# POWER_SUPPLY.net
KiCad netlist of a schematic drawn in Altium Designer
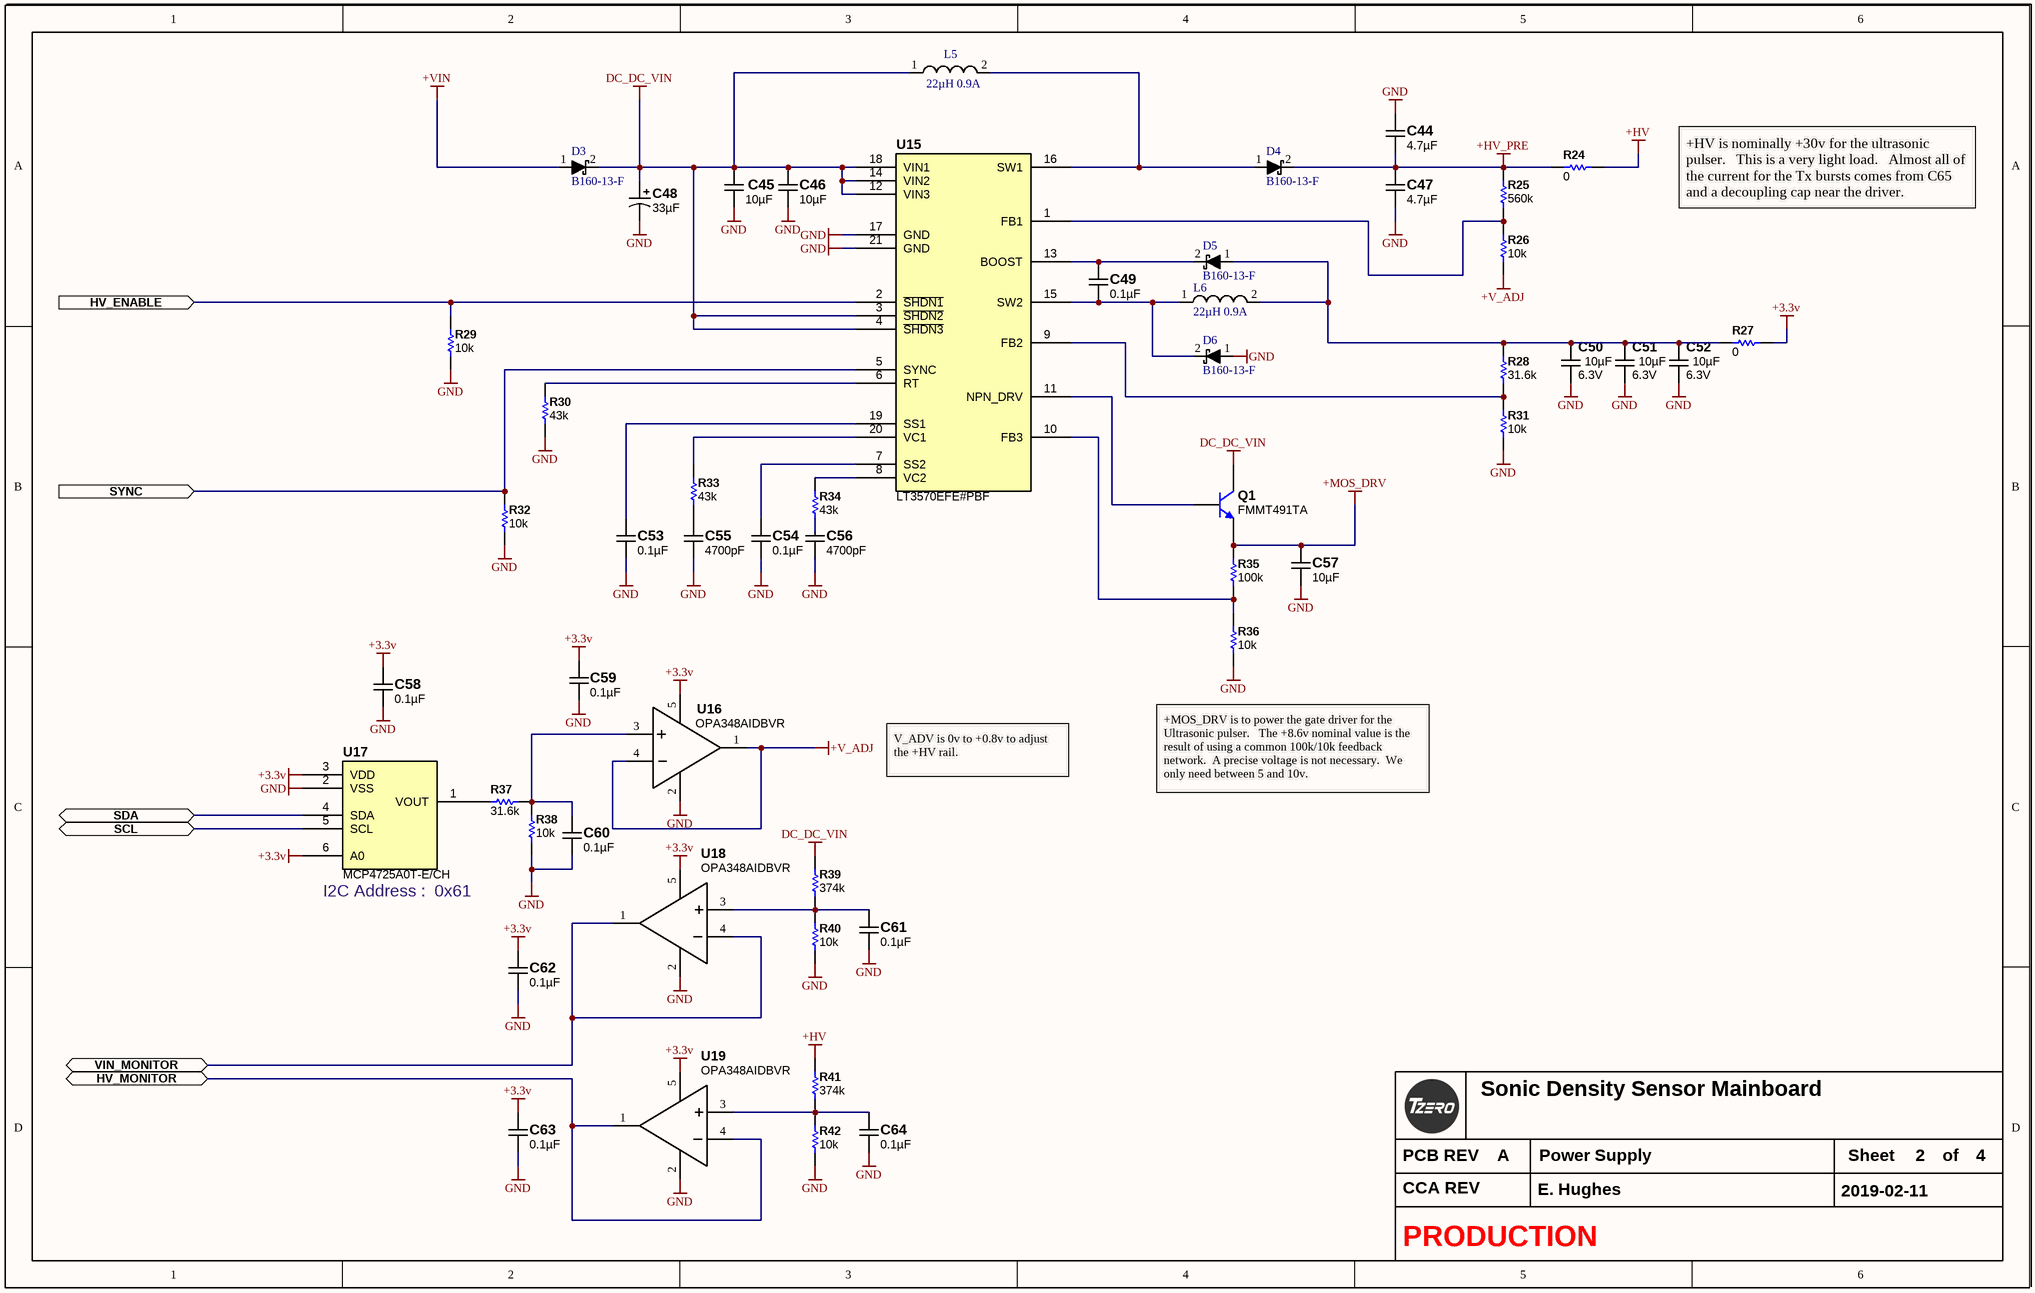
[diagram p0: POWER_SUPPLY.SchDoc]

(export (version "E")
  (design (tool "Eeschema 10.0.6"))
  (components
    (comp (ref "C44")
      (value "4.7µF")
      (footprint "C1210_2.80MM_HD")
      (description "CAP CER 4.7UF 50V X7R 1210")
      (fields
        (field (name "MANUFACTURER PART NUMBER") "CGA6P3X7R1H475M250AB")
        (field (name "MANUFACTURER") "TDK Corporation")
      )
      (libsource (lib "Capacitors - TDK- AEC-Q200") (part "C_2P_NP"))
    )
    (comp (ref "C45")
      (value "10µF")
      (footprint "C1206_1.90MM_HD")
      (description "CAP CER 10UF 35V X7R 1206")
      (fields
        (field (name "MANUFACTURER PART NUMBER") "CGA5L1X7R1V106K160AE")
        (field (name "MANUFACTURER") "TDK Corporation")
      )
      (libsource (lib "Capacitors - TDK- AEC-Q200") (part "C_2P_NP"))
    )
    (comp (ref "C46")
      (value "10µF")
      (footprint "C1206_1.90MM_HD")
      (description "CAP CER 10UF 35V X7R 1206")
      (fields
        (field (name "MANUFACTURER PART NUMBER") "CGA5L1X7R1V106K160AE")
        (field (name "MANUFACTURER") "TDK Corporation")
      )
      (libsource (lib "Capacitors - TDK- AEC-Q200") (part "C_2P_NP"))
    )
    (comp (ref "C47")
      (value "4.7µF")
      (footprint "C1210_2.80MM_HD")
      (description "CAP CER 4.7UF 50V X7R 1210")
      (fields
        (field (name "MANUFACTURER PART NUMBER") "CGA6P3X7R1H475M250AB")
        (field (name "MANUFACTURER") "TDK Corporation")
      )
      (libsource (lib "Capacitors - TDK- AEC-Q200") (part "C_2P_NP"))
    )
    (comp (ref "C48")
      (value "33µF")
      (footprint "C_ALU_C")
      (description "CAP ALUM 33UF 25V 20% SMD")
      (fields
        (field (name "MANUFACTURER PART NUMBER") "EEE-FK1E330UR")
        (field (name "MANUFACTURER") "Panasonic Electronic Components")
      )
      (libsource (lib "Capacitors") (part "C_2P_P"))
    )
    (comp (ref "C49")
      (value "0.1µF")
      (footprint "C0603_0.90MM_HD")
      (description "CAP CER 0.1UF 50V X7R 0603")
      (fields
        (field (name "MANUFACTURER PART NUMBER") "CGA3E2X7R1H104K080AE")
        (field (name "MANUFACTURER") "TDK Corporation")
      )
      (libsource (lib "Capacitors - TDK- AEC-Q200") (part "C_2P_NP"))
    )
    (comp (ref "C50")
      (value "10µF")
      (footprint "C0805_1.45MM_MD")
      (description "CAP CER 10UF 6.3V X7R 0805")
      (fields
        (field (name "MANUFACTURER PART NUMBER") "CGA4J1X7R0J106K125AC")
        (field (name "MANUFACTURER") "TDK Corporation")
        (field (name "VOLTAGE - RATED") "6.3V")
      )
      (libsource (lib "Capacitors - TDK- AEC-Q200") (part "C_2P_NP"))
    )
    (comp (ref "C51")
      (value "10µF")
      (footprint "C0805_1.45MM_MD")
      (description "CAP CER 10UF 6.3V X7R 0805")
      (fields
        (field (name "MANUFACTURER PART NUMBER") "CGA4J1X7R0J106K125AC")
        (field (name "MANUFACTURER") "TDK Corporation")
        (field (name "VOLTAGE - RATED") "6.3V")
      )
      (libsource (lib "Capacitors - TDK- AEC-Q200") (part "C_2P_NP"))
    )
    (comp (ref "C52")
      (value "10µF")
      (footprint "C0805_1.45MM_MD")
      (description "CAP CER 10UF 6.3V X7R 0805")
      (fields
        (field (name "MANUFACTURER PART NUMBER") "CGA4J1X7R0J106K125AC")
        (field (name "MANUFACTURER") "TDK Corporation")
        (field (name "VOLTAGE - RATED") "6.3V")
      )
      (libsource (lib "Capacitors - TDK- AEC-Q200") (part "C_2P_NP"))
    )
    (comp (ref "C53")
      (value "0.1µF")
      (footprint "C0603_0.90MM_HD")
      (description "CAP CER 0.1UF 50V X7R 0603")
      (fields
        (field (name "MANUFACTURER PART NUMBER") "CGA3E2X7R1H104K080AE")
        (field (name "MANUFACTURER") "TDK Corporation")
      )
      (libsource (lib "Capacitors - TDK- AEC-Q200") (part "C_2P_NP"))
    )
    (comp (ref "C54")
      (value "0.1µF")
      (footprint "C0603_0.90MM_HD")
      (description "CAP CER 0.1UF 50V X7R 0603")
      (fields
        (field (name "MANUFACTURER PART NUMBER") "CGA3E2X7R1H104K080AE")
        (field (name "MANUFACTURER") "TDK Corporation")
      )
      (libsource (lib "Capacitors - TDK- AEC-Q200") (part "C_2P_NP"))
    )
    (comp (ref "C55")
      (value "4700pF")
      (footprint "C0603_0.95MM_HD")
      (description "CAP CER 4700PF 50V X7R 0603")
      (fields
        (field (name "MANUFACTURER PART NUMBER") "CGA3E2X7R1H472K080AE")
        (field (name "MANUFACTURER") "TDK Corporation")
      )
      (libsource (lib "Capacitors - TDK- AEC-Q200") (part "C_2P_NP"))
    )
    (comp (ref "C56")
      (value "4700pF")
      (footprint "C0603_0.95MM_HD")
      (description "CAP CER 4700PF 50V X7R 0603")
      (fields
        (field (name "MANUFACTURER PART NUMBER") "CGA3E2X7R1H472K080AE")
        (field (name "MANUFACTURER") "TDK Corporation")
      )
      (libsource (lib "Capacitors - TDK- AEC-Q200") (part "C_2P_NP"))
    )
    (comp (ref "C57")
      (value "10µF")
      (footprint "C1206_1.90MM_HD")
      (description "CAP CER 10UF 35V X7R 1206")
      (fields
        (field (name "MANUFACTURER PART NUMBER") "CGA5L1X7R1V106K160AE")
        (field (name "MANUFACTURER") "TDK Corporation")
      )
      (libsource (lib "Capacitors - TDK- AEC-Q200") (part "C_2P_NP"))
    )
    (comp (ref "C58")
      (value "0.1µF")
      (footprint "C0603_0.90MM_HD")
      (description "CAP CER 0.1UF 50V X7R 0603")
      (fields
        (field (name "MANUFACTURER PART NUMBER") "CGA3E2X7R1H104K080AE")
        (field (name "MANUFACTURER") "TDK Corporation")
      )
      (libsource (lib "Capacitors - TDK- AEC-Q200") (part "C_2P_NP"))
    )
    (comp (ref "C59")
      (value "0.1µF")
      (footprint "C0603_0.90MM_HD")
      (description "CAP CER 0.1UF 50V X7R 0603")
      (fields
        (field (name "MANUFACTURER PART NUMBER") "CGA3E2X7R1H104K080AE")
        (field (name "MANUFACTURER") "TDK Corporation")
      )
      (libsource (lib "Capacitors - TDK- AEC-Q200") (part "C_2P_NP"))
    )
    (comp (ref "C60")
      (value "0.1µF")
      (footprint "C0603_0.90MM_HD")
      (description "CAP CER 0.1UF 50V X7R 0603")
      (fields
        (field (name "MANUFACTURER PART NUMBER") "CGA3E2X7R1H104K080AE")
        (field (name "MANUFACTURER") "TDK Corporation")
      )
      (libsource (lib "Capacitors - TDK- AEC-Q200") (part "C_2P_NP"))
    )
    (comp (ref "C61")
      (value "0.1µF")
      (footprint "C0603_0.90MM_HD")
      (description "CAP CER 0.1UF 50V X7R 0603")
      (fields
        (field (name "MANUFACTURER PART NUMBER") "CGA3E2X7R1H104K080AE")
        (field (name "MANUFACTURER") "TDK Corporation")
      )
      (libsource (lib "Capacitors - TDK- AEC-Q200") (part "C_2P_NP"))
    )
    (comp (ref "C62")
      (value "0.1µF")
      (footprint "C0603_0.90MM_HD")
      (description "CAP CER 0.1UF 50V X7R 0603")
      (fields
        (field (name "MANUFACTURER PART NUMBER") "CGA3E2X7R1H104K080AE")
        (field (name "MANUFACTURER") "TDK Corporation")
      )
      (libsource (lib "Capacitors - TDK- AEC-Q200") (part "C_2P_NP"))
    )
    (comp (ref "C63")
      (value "0.1µF")
      (footprint "C0603_0.90MM_HD")
      (description "CAP CER 0.1UF 50V X7R 0603")
      (fields
        (field (name "MANUFACTURER PART NUMBER") "CGA3E2X7R1H104K080AE")
        (field (name "MANUFACTURER") "TDK Corporation")
      )
      (libsource (lib "Capacitors - TDK- AEC-Q200") (part "C_2P_NP"))
    )
    (comp (ref "C64")
      (value "0.1µF")
      (footprint "C0603_0.90MM_HD")
      (description "CAP CER 0.1UF 50V X7R 0603")
      (fields
        (field (name "MANUFACTURER PART NUMBER") "CGA3E2X7R1H104K080AE")
        (field (name "MANUFACTURER") "TDK Corporation")
      )
      (libsource (lib "Capacitors - TDK- AEC-Q200") (part "C_2P_NP"))
    )
    (comp (ref "D3")
      (value "B160-13-F")
      (footprint "D_SMA_P")
      (description "DIODE SCHOTTKY 60V 1A SMA")
      (fields (field (name "MANUFACTURER") "Diodes Inc"))
      (libsource (lib "Diodes") (part "DS_1A_2C"))
    )
    (comp (ref "D4")
      (value "B160-13-F")
      (footprint "D_SMA_P")
      (description "DIODE SCHOTTKY 60V 1A SMA")
      (fields (field (name "MANUFACTURER") "Diodes Inc"))
      (libsource (lib "Diodes") (part "DS_1A_2C"))
    )
    (comp (ref "D5")
      (value "B160-13-F")
      (footprint "D_SMA_P")
      (description "DIODE SCHOTTKY 60V 1A SMA")
      (fields (field (name "MANUFACTURER") "Diodes Inc"))
      (libsource (lib "Diodes") (part "DS_1A_2C"))
    )
    (comp (ref "D6")
      (value "B160-13-F")
      (footprint "D_SMA_P")
      (description "DIODE SCHOTTKY 60V 1A SMA")
      (fields (field (name "MANUFACTURER") "Diodes Inc"))
      (libsource (lib "Diodes") (part "DS_1A_2C"))
    )
    (comp (ref "L5")
      (value "22µH 0.9A")
      (footprint "L_NRS5020")
      (description "Inductor 22µH 0.9A")
      (fields (field (name "PART NUMBER") "NRS5020T220MMGJ") (field (name "MANUFACTURER") "Taiyo Yuden"))
      (libsource (lib "Inductors") (part "L_2P"))
    )
    (comp (ref "L6")
      (value "22µH 0.9A")
      (footprint "L_NRS5020")
      (description "Inductor 22µH 0.9A")
      (fields (field (name "PART NUMBER") "NRS5020T220MMGJ") (field (name "MANUFACTURER") "Taiyo Yuden"))
      (libsource (lib "Inductors") (part "L_2P"))
    )
    (comp (ref "Q1")
      (value "FMMT491TA")
      (footprint "SOT-23")
      (description "TRANS NPN 60V 1A SOT23-3")
      (fields (field (name "MANUFACTURER") "Diodes Zetex"))
      (libsource (lib "eTransistor") (part "FMMT491TA"))
    )
    (comp (ref "R24")
      (value "0")
      (footprint "R0603_0.55MM_HD")
      (description "RES 0.0 OHM 1/10W JUMP 0603 SMD")
      (fields
        (field (name "MANUFACTURER PART NUMBER") "ERJ-3GEY0R00V")
        (field (name "MANUFACTURER") "Panasonic Electronic Components")
      )
      (libsource (lib "Resistors - Panasonic - AEC-Q200") (part "R_2P"))
    )
    (comp (ref "R25")
      (value "560k")
      (footprint "R0603_0.55MM_HD")
      (description "RES 560K OHM 1/10W 1% 0603 SMD")
      (fields
        (field (name "MANUFACTURER PART NUMBER") "ERJ-3EKF5603V")
        (field (name "MANUFACTURER") "Panasonic Electronic Components")
      )
      (libsource (lib "Resistors - Panasonic - AEC-Q200") (part "R_2P"))
    )
    (comp (ref "R26")
      (value "10k")
      (footprint "R0603_0.55MM_HD")
      (description "RES 10K OHM 1/10W 1% 0603 SMD")
      (fields
        (field (name "MANUFACTURER PART NUMBER") "ERJ-3EKF1002V")
        (field (name "MANUFACTURER") "Panasonic Electronic Components")
      )
      (libsource (lib "Resistors - Panasonic - AEC-Q200") (part "R_2P"))
    )
    (comp (ref "R27")
      (value "0")
      (footprint "R0603_0.55MM_HD")
      (description "RES 0.0 OHM 1/10W JUMP 0603 SMD")
      (fields
        (field (name "MANUFACTURER PART NUMBER") "ERJ-3GEY0R00V")
        (field (name "MANUFACTURER") "Panasonic Electronic Components")
      )
      (libsource (lib "Resistors - Panasonic - AEC-Q200") (part "R_2P"))
    )
    (comp (ref "R28")
      (value "31.6k")
      (footprint "R0603_0.55MM_HD")
      (description "RES 31.6K OHM 1/10W 1% 0603 SMD")
      (fields
        (field (name "MANUFACTURER PART NUMBER") "ERJ-3EKF3162V")
        (field (name "MANUFACTURER") "Panasonic Electronic Components")
      )
      (libsource (lib "Resistors - Panasonic - AEC-Q200") (part "R_2P"))
    )
    (comp (ref "R29")
      (value "10k")
      (footprint "R0603_0.55MM_HD")
      (description "RES 10K OHM 1/10W 1% 0603 SMD")
      (fields
        (field (name "MANUFACTURER PART NUMBER") "ERJ-3EKF1002V")
        (field (name "MANUFACTURER") "Panasonic Electronic Components")
      )
      (libsource (lib "Resistors - Panasonic - AEC-Q200") (part "R_2P"))
    )
    (comp (ref "R30")
      (value "43k")
      (footprint "R0603_0.55MM_HD")
      (description "RES 43K OHM 1/10W 1% 0603 SMD")
      (fields
        (field (name "MANUFACTURER PART NUMBER") "ERJ-3EKF4302V")
        (field (name "MANUFACTURER") "Panasonic Electronic Components")
      )
      (libsource (lib "Resistors - Panasonic - AEC-Q200") (part "R_2P"))
    )
    (comp (ref "R31")
      (value "10k")
      (footprint "R0603_0.55MM_HD")
      (description "RES 10K OHM 1/10W 1% 0603 SMD")
      (fields
        (field (name "MANUFACTURER PART NUMBER") "ERJ-3EKF1002V")
        (field (name "MANUFACTURER") "Panasonic Electronic Components")
      )
      (libsource (lib "Resistors - Panasonic - AEC-Q200") (part "R_2P"))
    )
    (comp (ref "R32")
      (value "10k")
      (footprint "R0603_0.55MM_HD")
      (description "RES 10K OHM 1/10W 1% 0603 SMD")
      (fields
        (field (name "MANUFACTURER PART NUMBER") "ERJ-3EKF1002V")
        (field (name "MANUFACTURER") "Panasonic Electronic Components")
      )
      (libsource (lib "Resistors - Panasonic - AEC-Q200") (part "R_2P"))
    )
    (comp (ref "R33")
      (value "43k")
      (footprint "R0603_0.55MM_HD")
      (description "RES 43K OHM 1/10W 1% 0603 SMD")
      (fields
        (field (name "MANUFACTURER PART NUMBER") "ERJ-3EKF4302V")
        (field (name "MANUFACTURER") "Panasonic Electronic Components")
      )
      (libsource (lib "Resistors - Panasonic - AEC-Q200") (part "R_2P"))
    )
    (comp (ref "R34")
      (value "43k")
      (footprint "R0603_0.55MM_HD")
      (description "RES 43K OHM 1/10W 1% 0603 SMD")
      (fields
        (field (name "MANUFACTURER PART NUMBER") "ERJ-3EKF4302V")
        (field (name "MANUFACTURER") "Panasonic Electronic Components")
      )
      (libsource (lib "Resistors - Panasonic - AEC-Q200") (part "R_2P"))
    )
    (comp (ref "R35")
      (value "100k")
      (footprint "R0603_0.55MM_HD")
      (description "RES 100K OHM 1/10W 1% 0603 SMD")
      (fields
        (field (name "MANUFACTURER PART NUMBER") "ERJ-3EKF1003V")
        (field (name "MANUFACTURER") "Panasonic Electronic Components")
      )
      (libsource (lib "Resistors - Panasonic - AEC-Q200") (part "R_2P"))
    )
    (comp (ref "R36")
      (value "10k")
      (footprint "R0603_0.55MM_HD")
      (description "RES 10K OHM 1/10W 1% 0603 SMD")
      (fields
        (field (name "MANUFACTURER PART NUMBER") "ERJ-3EKF1002V")
        (field (name "MANUFACTURER") "Panasonic Electronic Components")
      )
      (libsource (lib "Resistors - Panasonic - AEC-Q200") (part "R_2P"))
    )
    (comp (ref "R37")
      (value "31.6k")
      (footprint "R0603_0.55MM_HD")
      (description "RES 31.6K OHM 1/10W 1% 0603 SMD")
      (fields
        (field (name "MANUFACTURER PART NUMBER") "ERJ-3EKF3162V")
        (field (name "MANUFACTURER") "Panasonic Electronic Components")
      )
      (libsource (lib "Resistors - Panasonic - AEC-Q200") (part "R_2P"))
    )
    (comp (ref "R38")
      (value "10k")
      (footprint "R0603_0.55MM_HD")
      (description "RES 10K OHM 1/10W 1% 0603 SMD")
      (fields
        (field (name "MANUFACTURER PART NUMBER") "ERJ-3EKF1002V")
        (field (name "MANUFACTURER") "Panasonic Electronic Components")
      )
      (libsource (lib "Resistors - Panasonic - AEC-Q200") (part "R_2P"))
    )
    (comp (ref "R39")
      (value "374k")
      (footprint "R0603_0.55MM_HD")
      (description "RES 374K OHM 1/10W 1% 0603 SMD")
      (fields
        (field (name "MANUFACTURER PART NUMBER") "ERJ-3EKF3743V")
        (field (name "MANUFACTURER") "Panasonic Electronic Components")
      )
      (libsource (lib "Resistors - Panasonic - AEC-Q200") (part "R_2P"))
    )
    (comp (ref "R40")
      (value "10k")
      (footprint "R0603_0.55MM_HD")
      (description "RES 10K OHM 1/10W 1% 0603 SMD")
      (fields
        (field (name "MANUFACTURER PART NUMBER") "ERJ-3EKF1002V")
        (field (name "MANUFACTURER") "Panasonic Electronic Components")
      )
      (libsource (lib "Resistors - Panasonic - AEC-Q200") (part "R_2P"))
    )
    (comp (ref "R41")
      (value "374k")
      (footprint "R0603_0.55MM_HD")
      (description "RES 374K OHM 1/10W 1% 0603 SMD")
      (fields
        (field (name "MANUFACTURER PART NUMBER") "ERJ-3EKF3743V")
        (field (name "MANUFACTURER") "Panasonic Electronic Components")
      )
      (libsource (lib "Resistors - Panasonic - AEC-Q200") (part "R_2P"))
    )
    (comp (ref "R42")
      (value "10k")
      (footprint "R0603_0.55MM_HD")
      (description "RES 10K OHM 1/10W 1% 0603 SMD")
      (fields
        (field (name "MANUFACTURER PART NUMBER") "ERJ-3EKF1002V")
        (field (name "MANUFACTURER") "Panasonic Electronic Components")
      )
      (libsource (lib "Resistors - Panasonic - AEC-Q200") (part "R_2P"))
    )
    (comp (ref "U15")
      (value "LT3570EFE#PBF")
      (footprint "TSOP65P640X120_HS-21N")
      (description "IC REG BUCK/BST/LINEAR 20TSSOP")
      (fields (field (name "MANUFACTURER") "Linear Technology"))
      (libsource (lib "eIC") (part "LT3570EFE#PBF"))
    )
    (comp (ref "U16")
      (value "OPA348AIDBVR")
      (footprint "SOT23-5")
      (description "IC OPAMP GP 1MHZ RRO SOT23-5")
      (fields (field (name "MANUFACTURER") "Texas Instruments"))
      (libsource (lib "eOPAMP") (part "OPA348AIDBVR"))
    )
    (comp (ref "U17")
      (value "MCP4725A0T-E/CH")
      (footprint "SOT95P245X145-6L")
      (description "IC DAC 12BIT W/I2C SOT23A-6")
      (fields (field (name "MANUFACTURER") "Microchip"))
      (libsource (lib "eIC") (part "MCP4725A0T-E/CH"))
    )
    (comp (ref "U18")
      (value "OPA348AIDBVR")
      (footprint "SOT23-5")
      (description "IC OPAMP GP 1MHZ RRO SOT23-5")
      (fields (field (name "MANUFACTURER") "Texas Instruments"))
      (libsource (lib "eOPAMP") (part "OPA348AIDBVR"))
    )
    (comp (ref "U19")
      (value "OPA348AIDBVR")
      (footprint "SOT23-5")
      (description "IC OPAMP GP 1MHZ RRO SOT23-5")
      (fields (field (name "MANUFACTURER") "Texas Instruments"))
      (libsource (lib "eOPAMP") (part "OPA348AIDBVR"))
    )
  )
  (nets
    (net (code "1") (name "+3.3v") (class "Default")
      (node (ref "C58") (pin "2") (pinfunction "1_2") (pintype "passive"))
      (node (ref "C59") (pin "2") (pinfunction "1_2") (pintype "passive"))
      (node (ref "C62") (pin "2") (pinfunction "1_2") (pintype "passive"))
      (node (ref "C63") (pin "2") (pinfunction "1_2") (pintype "passive"))
      (node (ref "R27") (pin "1") (pinfunction "1_1") (pintype "passive"))
      (node (ref "U16") (pin "5") (pinfunction "VCC_5") (pintype "passive"))
      (node (ref "U17") (pin "3") (pinfunction "VDD_3") (pintype "passive"))
      (node (ref "U17") (pin "6") (pinfunction "A0_6") (pintype "passive"))
      (node (ref "U18") (pin "5") (pinfunction "VCC_5") (pintype "passive"))
      (node (ref "U19") (pin "5") (pinfunction "VCC_5") (pintype "passive"))
    )
    (net (code "2") (name "+HV") (class "Default")
      (node (ref "R24") (pin "1") (pinfunction "1_1") (pintype "passive"))
      (node (ref "R41") (pin "2") (pinfunction "2_2") (pintype "passive"))
    )
    (net (code "3") (name "+HV_PRE") (class "Default")
      (node (ref "C44") (pin "1") (pinfunction "1_1") (pintype "passive"))
      (node (ref "C47") (pin "2") (pinfunction "1_2") (pintype "passive"))
      (node (ref "D4") (pin "2") (pinfunction "K_2") (pintype "passive"))
      (node (ref "R24") (pin "2") (pinfunction "2_2") (pintype "passive"))
      (node (ref "R25") (pin "2") (pinfunction "2_2") (pintype "passive"))
    )
    (net (code "4") (name "+MOS_DRV") (class "Default")
      (node (ref "C57") (pin "2") (pinfunction "1_2") (pintype "passive"))
      (node (ref "Q1") (pin "2") (pinfunction "E_2") (pintype "passive"))
      (node (ref "R35") (pin "2") (pinfunction "2_2") (pintype "passive"))
    )
    (net (code "5") (name "+VIN") (class "Default")
      (node (ref "D3") (pin "1") (pinfunction "A_1") (pintype "passive"))
    )
    (net (code "6") (name "+V_ADJ") (class "Default")
      (node (ref "R26") (pin "1") (pinfunction "1_1") (pintype "passive"))
      (node (ref "U16") (pin "1") (pinfunction "OUT_1") (pintype "passive"))
      (node (ref "U16") (pin "4") (pinfunction "-_4") (pintype "passive"))
    )
    (net (code "7") (name "/HV_ENABLE") (class "Default")
      (node (ref "R29") (pin "2") (pinfunction "2_2") (pintype "passive"))
      (node (ref "U15") (pin "2") (pinfunction "~{SHDN1}_2") (pintype "passive"))
    )
    (net (code "8") (name "/HV_MONITOR") (class "Default")
      (node (ref "U19") (pin "1") (pinfunction "OUT_1") (pintype "passive"))
      (node (ref "U19") (pin "4") (pinfunction "-_4") (pintype "passive"))
    )
    (net (code "9") (name "/SCL") (class "Default")
      (node (ref "U17") (pin "5") (pinfunction "SCL_5") (pintype "passive"))
    )
    (net (code "10") (name "/SDA") (class "Default")
      (node (ref "U17") (pin "4") (pinfunction "SDA_4") (pintype "passive"))
    )
    (net (code "11") (name "/SYNC") (class "Default")
      (node (ref "R32") (pin "2") (pinfunction "2_2") (pintype "passive"))
      (node (ref "U15") (pin "5") (pinfunction "SYNC_5") (pintype "passive"))
    )
    (net (code "12") (name "/VIN_MONITOR") (class "Default")
      (node (ref "U18") (pin "1") (pinfunction "OUT_1") (pintype "passive"))
      (node (ref "U18") (pin "4") (pinfunction "-_4") (pintype "passive"))
    )
    (net (code "13") (name "DC_DC_VIN") (class "Default")
      (node (ref "C45") (pin "2") (pinfunction "1_2") (pintype "passive"))
      (node (ref "C46") (pin "2") (pinfunction "1_2") (pintype "passive"))
      (node (ref "C48") (pin "1") (pinfunction "1_1") (pintype "passive"))
      (node (ref "D3") (pin "2") (pinfunction "K_2") (pintype "passive"))
      (node (ref "L5") (pin "1") (pinfunction "1_1") (pintype "passive"))
      (node (ref "Q1") (pin "3") (pinfunction "C_3") (pintype "passive"))
      (node (ref "R39") (pin "2") (pinfunction "2_2") (pintype "passive"))
      (node (ref "U15") (pin "12") (pinfunction "VIN3_12") (pintype "passive"))
      (node (ref "U15") (pin "14") (pinfunction "VIN2_14") (pintype "passive"))
      (node (ref "U15") (pin "18") (pinfunction "VIN1_18") (pintype "passive"))
      (node (ref "U15") (pin "3") (pinfunction "~{SHDN2}_3") (pintype "passive"))
      (node (ref "U15") (pin "4") (pinfunction "~{SHDN3}_4") (pintype "passive"))
    )
    (net (code "14") (name "GND") (class "Default")
      (node (ref "C44") (pin "2") (pinfunction "1_2") (pintype "passive"))
      (node (ref "C45") (pin "1") (pinfunction "1_1") (pintype "passive"))
      (node (ref "C46") (pin "1") (pinfunction "1_1") (pintype "passive"))
      (node (ref "C47") (pin "1") (pinfunction "1_1") (pintype "passive"))
      (node (ref "C48") (pin "2") (pinfunction "1_2") (pintype "passive"))
      (node (ref "C50") (pin "1") (pinfunction "1_1") (pintype "passive"))
      (node (ref "C51") (pin "1") (pinfunction "1_1") (pintype "passive"))
      (node (ref "C52") (pin "1") (pinfunction "1_1") (pintype "passive"))
      (node (ref "C53") (pin "1") (pinfunction "1_1") (pintype "passive"))
      (node (ref "C54") (pin "1") (pinfunction "1_1") (pintype "passive"))
      (node (ref "C55") (pin "1") (pinfunction "1_1") (pintype "passive"))
      (node (ref "C56") (pin "1") (pinfunction "1_1") (pintype "passive"))
      (node (ref "C57") (pin "1") (pinfunction "1_1") (pintype "passive"))
      (node (ref "C58") (pin "1") (pinfunction "1_1") (pintype "passive"))
      (node (ref "C59") (pin "1") (pinfunction "1_1") (pintype "passive"))
      (node (ref "C60") (pin "1") (pinfunction "1_1") (pintype "passive"))
      (node (ref "C61") (pin "1") (pinfunction "1_1") (pintype "passive"))
      (node (ref "C62") (pin "1") (pinfunction "1_1") (pintype "passive"))
      (node (ref "C63") (pin "1") (pinfunction "1_1") (pintype "passive"))
      (node (ref "C64") (pin "1") (pinfunction "1_1") (pintype "passive"))
      (node (ref "D6") (pin "1") (pinfunction "A_1") (pintype "passive"))
      (node (ref "R29") (pin "1") (pinfunction "1_1") (pintype "passive"))
      (node (ref "R30") (pin "1") (pinfunction "1_1") (pintype "passive"))
      (node (ref "R31") (pin "1") (pinfunction "1_1") (pintype "passive"))
      (node (ref "R32") (pin "1") (pinfunction "1_1") (pintype "passive"))
      (node (ref "R36") (pin "1") (pinfunction "1_1") (pintype "passive"))
      (node (ref "R38") (pin "1") (pinfunction "1_1") (pintype "passive"))
      (node (ref "R40") (pin "1") (pinfunction "1_1") (pintype "passive"))
      (node (ref "R42") (pin "1") (pinfunction "1_1") (pintype "passive"))
      (node (ref "U15") (pin "17") (pinfunction "GND_17") (pintype "passive"))
      (node (ref "U15") (pin "21") (pinfunction "GND_21") (pintype "passive"))
      (node (ref "U16") (pin "2") (pinfunction "GND_2") (pintype "passive"))
      (node (ref "U17") (pin "2") (pinfunction "VSS_2") (pintype "passive"))
      (node (ref "U18") (pin "2") (pinfunction "GND_2") (pintype "passive"))
      (node (ref "U19") (pin "2") (pinfunction "GND_2") (pintype "passive"))
    )
    (net (code "15") (name "Net-(C55-1-Pad2)") (class "Default")
      (node (ref "C55") (pin "2") (pinfunction "1_2") (pintype "passive"))
      (node (ref "R33") (pin "1") (pinfunction "1_1") (pintype "passive"))
    )
    (net (code "16") (name "Net-(C56-1-Pad2)") (class "Default")
      (node (ref "C56") (pin "2") (pinfunction "1_2") (pintype "passive"))
      (node (ref "R34") (pin "1") (pinfunction "1_1") (pintype "passive"))
    )
    (net (code "17") (name "Net-(D4-A)") (class "Default")
      (node (ref "D4") (pin "1") (pinfunction "A_1") (pintype "passive"))
      (node (ref "L5") (pin "2") (pinfunction "2_2") (pintype "passive"))
      (node (ref "U15") (pin "16") (pinfunction "SW1_16") (pintype "passive"))
    )
    (net (code "18") (name "Net-(D5-A)") (class "Default")
      (node (ref "C50") (pin "2") (pinfunction "1_2") (pintype "passive"))
      (node (ref "C51") (pin "2") (pinfunction "1_2") (pintype "passive"))
      (node (ref "C52") (pin "2") (pinfunction "1_2") (pintype "passive"))
      (node (ref "D5") (pin "1") (pinfunction "A_1") (pintype "passive"))
      (node (ref "L6") (pin "2") (pinfunction "2_2") (pintype "passive"))
      (node (ref "R27") (pin "2") (pinfunction "2_2") (pintype "passive"))
      (node (ref "R28") (pin "2") (pinfunction "2_2") (pintype "passive"))
    )
    (net (code "19") (name "Net-(D5-K)") (class "Default")
      (node (ref "C49") (pin "2") (pinfunction "1_2") (pintype "passive"))
      (node (ref "D5") (pin "2") (pinfunction "K_2") (pintype "passive"))
      (node (ref "U15") (pin "13") (pinfunction "BOOST_13") (pintype "passive"))
    )
    (net (code "20") (name "Net-(D6-K)") (class "Default")
      (node (ref "C49") (pin "1") (pinfunction "1_1") (pintype "passive"))
      (node (ref "D6") (pin "2") (pinfunction "K_2") (pintype "passive"))
      (node (ref "L6") (pin "1") (pinfunction "1_1") (pintype "passive"))
      (node (ref "U15") (pin "15") (pinfunction "SW2_15") (pintype "passive"))
    )
    (net (code "21") (name "Net-(Q1-B)") (class "Default")
      (node (ref "Q1") (pin "1") (pinfunction "B_1") (pintype "passive"))
      (node (ref "U15") (pin "11") (pinfunction "NPN_DRV_11") (pintype "passive"))
    )
    (net (code "22") (name "Net-(U15-FB1)") (class "Default")
      (node (ref "R25") (pin "1") (pinfunction "1_1") (pintype "passive"))
      (node (ref "R26") (pin "2") (pinfunction "2_2") (pintype "passive"))
      (node (ref "U15") (pin "1") (pinfunction "FB1_1") (pintype "passive"))
    )
    (net (code "23") (name "Net-(U15-FB2)") (class "Default")
      (node (ref "R28") (pin "1") (pinfunction "1_1") (pintype "passive"))
      (node (ref "R31") (pin "2") (pinfunction "2_2") (pintype "passive"))
      (node (ref "U15") (pin "9") (pinfunction "FB2_9") (pintype "passive"))
    )
    (net (code "24") (name "Net-(U15-FB3)") (class "Default")
      (node (ref "R35") (pin "1") (pinfunction "1_1") (pintype "passive"))
      (node (ref "R36") (pin "2") (pinfunction "2_2") (pintype "passive"))
      (node (ref "U15") (pin "10") (pinfunction "FB3_10") (pintype "passive"))
    )
    (net (code "25") (name "Net-(U15-RT)") (class "Default")
      (node (ref "R30") (pin "2") (pinfunction "2_2") (pintype "passive"))
      (node (ref "U15") (pin "6") (pinfunction "RT_6") (pintype "passive"))
    )
    (net (code "26") (name "Net-(U15-SS1)") (class "Default")
      (node (ref "C53") (pin "2") (pinfunction "1_2") (pintype "passive"))
      (node (ref "U15") (pin "19") (pinfunction "SS1_19") (pintype "passive"))
    )
    (net (code "27") (name "Net-(U15-SS2)") (class "Default")
      (node (ref "C54") (pin "2") (pinfunction "1_2") (pintype "passive"))
      (node (ref "U15") (pin "7") (pinfunction "SS2_7") (pintype "passive"))
    )
    (net (code "28") (name "Net-(U15-VC1)") (class "Default")
      (node (ref "R33") (pin "2") (pinfunction "2_2") (pintype "passive"))
      (node (ref "U15") (pin "20") (pinfunction "VC1_20") (pintype "passive"))
    )
    (net (code "29") (name "Net-(U15-VC2)") (class "Default")
      (node (ref "R34") (pin "2") (pinfunction "2_2") (pintype "passive"))
      (node (ref "U15") (pin "8") (pinfunction "VC2_8") (pintype "passive"))
    )
    (net (code "30") (name "Net-(U16-+)") (class "Default")
      (node (ref "C60") (pin "2") (pinfunction "1_2") (pintype "passive"))
      (node (ref "R37") (pin "1") (pinfunction "1_1") (pintype "passive"))
      (node (ref "R38") (pin "2") (pinfunction "2_2") (pintype "passive"))
      (node (ref "U16") (pin "3") (pinfunction "+_3") (pintype "passive"))
    )
    (net (code "31") (name "Net-(U17-VOUT)") (class "Default")
      (node (ref "R37") (pin "2") (pinfunction "2_2") (pintype "passive"))
      (node (ref "U17") (pin "1") (pinfunction "VOUT_1") (pintype "passive"))
    )
    (net (code "32") (name "Net-(U18-+)") (class "Default")
      (node (ref "C61") (pin "2") (pinfunction "1_2") (pintype "passive"))
      (node (ref "R39") (pin "1") (pinfunction "1_1") (pintype "passive"))
      (node (ref "R40") (pin "2") (pinfunction "2_2") (pintype "passive"))
      (node (ref "U18") (pin "3") (pinfunction "+_3") (pintype "passive"))
    )
    (net (code "33") (name "Net-(U19-+)") (class "Default")
      (node (ref "C64") (pin "2") (pinfunction "1_2") (pintype "passive"))
      (node (ref "R41") (pin "1") (pinfunction "1_1") (pintype "passive"))
      (node (ref "R42") (pin "2") (pinfunction "2_2") (pintype "passive"))
      (node (ref "U19") (pin "3") (pinfunction "+_3") (pintype "passive"))
    )
  )
)
